# Zio_Qwiic_Relay.net
KiCad netlist of a schematic drawn in EAGLE
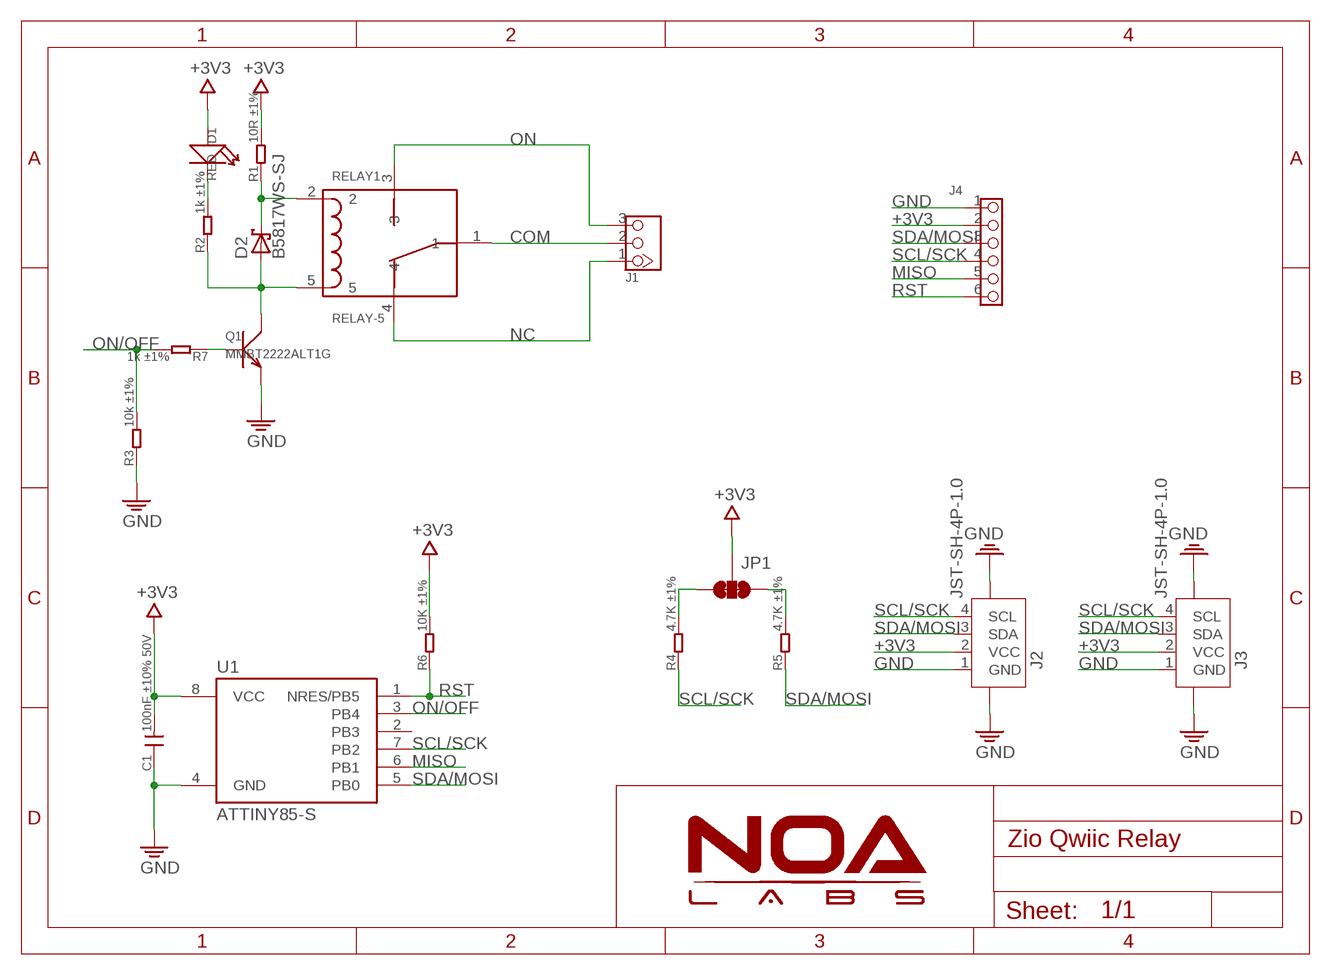
[diagram p0: schematic, sheet 1]

(export (version "E")
  (design (tool "Eeschema 10.0.6"))
  (components
    (comp (ref "C1")
      (value "100nF ±10% 50V")
      (footprint "eagle-import:C0603")
      (libsource (lib "eagle-import") (part "C-0603"))
    )
    (comp (ref "D1")
      (value "RED")
      (footprint "eagle-import:LED-0603")
      (libsource (lib "eagle-import") (part "LED'0603'"))
    )
    (comp (ref "D2")
      (value "B5817WS-SJ")
      (footprint "eagle-import:SOD323")
      (libsource (lib "eagle-import") (part "SCHOTTKY-SOD323"))
    )
    (comp (ref "J1")
      (value "HEADER-3P")
      (footprint "eagle-import:3P-SCREW-5.08")
      (libsource (lib "eagle-import") (part "HEADER-3P"))
    )
    (comp (ref "J2")
      (value "JST-SH-4P-1.0")
      (footprint "eagle-import:JST-SH-4P")
      (libsource (lib "eagle-import") (part "JST-SH-4P-1.0"))
    )
    (comp (ref "J3")
      (value "JST-SH-4P-1.0")
      (footprint "eagle-import:JST-SH-4P")
      (libsource (lib "eagle-import") (part "JST-SH-4P-1.0"))
    )
    (comp (ref "J4")
      (value "HEADER-6P-60/35MIL")
      (footprint "eagle-import:6P-2.54-60_35MIL")
      (libsource (lib "eagle-import") (part "HEADER-6P-60/35MIL"))
    )
    (comp (ref "JP1")
      (value "SMT-JUMPER_3_2-NC_TRACE")
      (footprint "eagle-import:SMT-JUMPER_3_2-NC_TRACE")
      (libsource (lib "eagle-import") (part "SMT-JUMPER_3_2-NC_TRACE"))
    )
    (comp (ref "Q1")
      (value "MMBT2222ALT1G")
      (footprint "eagle-import:SOT23")
      (libsource (lib "eagle-import") (part "TRANSISTOR-NPN-SOT23''"))
    )
    (comp (ref "R1")
      (value "10R ±1%")
      (footprint "eagle-import:R0603")
      (libsource (lib "eagle-import") (part "R-0603"))
    )
    (comp (ref "R2")
      (value "1k ±1%")
      (footprint "eagle-import:R0603")
      (libsource (lib "eagle-import") (part "R-0603"))
    )
    (comp (ref "R3")
      (value "10k ±1%")
      (footprint "eagle-import:R0603")
      (libsource (lib "eagle-import") (part "R-0603"))
    )
    (comp (ref "R4")
      (value "4.7K ±1%")
      (footprint "eagle-import:R0603")
      (libsource (lib "eagle-import") (part "R-0603"))
    )
    (comp (ref "R5")
      (value "4.7K ±1%")
      (footprint "eagle-import:R0603")
      (libsource (lib "eagle-import") (part "R-0603"))
    )
    (comp (ref "R6")
      (value "10K ±1%")
      (footprint "eagle-import:R0603")
      (libsource (lib "eagle-import") (part "R-0603"))
    )
    (comp (ref "R7")
      (value "1k ±1%")
      (footprint "eagle-import:R0603")
      (libsource (lib "eagle-import") (part "R-0603"))
    )
    (comp (ref "RELAY1")
      (value "RELAY-5")
      (footprint "eagle-import:RELAY-5")
      (libsource (lib "eagle-import") (part "RELAY-5"))
    )
    (comp (ref "U1")
      (value "ATTINY85-S")
      (footprint "eagle-import:SOIC8_EIAJ_208MIL")
      (libsource (lib "eagle-import") (part "ATTINY85S-"))
    )
  )
  (nets
    (net (code "1") (name "+3V3") (class "Default")
      (node (ref "C1") (pin "2") (pinfunction "2_2") (pintype "passive"))
      (node (ref "D1") (pin "+") (pinfunction "+_+") (pintype "passive"))
      (node (ref "J2") (pin "2") (pinfunction "VCC_2") (pintype "bidirectional"))
      (node (ref "J3") (pin "2") (pinfunction "VCC_2") (pintype "bidirectional"))
      (node (ref "J4") (pin "2") (pinfunction "2_2") (pintype "bidirectional"))
      (node (ref "JP1") (pin "2") (pinfunction "2_2") (pintype "passive"))
      (node (ref "R1") (pin "2") (pinfunction "2_2") (pintype "passive"))
      (node (ref "R6") (pin "2") (pinfunction "2_2") (pintype "passive"))
      (node (ref "U1") (pin "8") (pinfunction "VCC_8") (pintype "power_in"))
    )
    (net (code "2") (name "/COM") (class "Default")
      (node (ref "J1") (pin "2") (pinfunction "P$2_2") (pintype "bidirectional"))
      (node (ref "RELAY1") (pin "1") (pinfunction "1_1") (pintype "bidirectional"))
    )
    (net (code "3") (name "/MISO") (class "Default")
      (node (ref "J4") (pin "5") (pinfunction "5_5") (pintype "bidirectional"))
      (node (ref "U1") (pin "6") (pinfunction "PB1_6") (pintype "bidirectional"))
    )
    (net (code "4") (name "/NC") (class "Default")
      (node (ref "J1") (pin "1") (pinfunction "P$1_1") (pintype "bidirectional"))
      (node (ref "RELAY1") (pin "4") (pinfunction "4_4") (pintype "bidirectional"))
    )
    (net (code "5") (name "/ON") (class "Default")
      (node (ref "J1") (pin "3") (pinfunction "P$3_3") (pintype "bidirectional"))
      (node (ref "RELAY1") (pin "3") (pinfunction "3_3") (pintype "bidirectional"))
    )
    (net (code "6") (name "/ON{slash}OFF") (class "Default")
      (node (ref "R3") (pin "2") (pinfunction "2_2") (pintype "passive"))
      (node (ref "R7") (pin "2") (pinfunction "2_2") (pintype "passive"))
      (node (ref "U1") (pin "3") (pinfunction "PB4_3") (pintype "bidirectional"))
    )
    (net (code "7") (name "/RST") (class "Default")
      (node (ref "J4") (pin "6") (pinfunction "6_6") (pintype "bidirectional"))
      (node (ref "R6") (pin "1") (pinfunction "1_1") (pintype "passive"))
      (node (ref "U1") (pin "1") (pinfunction "NRES/PB5_1") (pintype "bidirectional"))
    )
    (net (code "8") (name "/SCL{slash}SCK") (class "Default")
      (node (ref "J2") (pin "4") (pinfunction "SCL_4") (pintype "bidirectional"))
      (node (ref "J3") (pin "4") (pinfunction "SCL_4") (pintype "bidirectional"))
      (node (ref "J4") (pin "4") (pinfunction "4_4") (pintype "bidirectional"))
      (node (ref "R4") (pin "1") (pinfunction "1_1") (pintype "passive"))
      (node (ref "U1") (pin "7") (pinfunction "PB2_7") (pintype "bidirectional"))
    )
    (net (code "9") (name "/SDA{slash}MOSI") (class "Default")
      (node (ref "J2") (pin "3") (pinfunction "SDA_3") (pintype "bidirectional"))
      (node (ref "J3") (pin "3") (pinfunction "SDA_3") (pintype "bidirectional"))
      (node (ref "J4") (pin "3") (pinfunction "3_3") (pintype "bidirectional"))
      (node (ref "R5") (pin "1") (pinfunction "1_1") (pintype "passive"))
      (node (ref "U1") (pin "5") (pinfunction "PB0_5") (pintype "bidirectional"))
    )
    (net (code "10") (name "GND") (class "Default")
      (node (ref "C1") (pin "1") (pinfunction "1_1") (pintype "passive"))
      (node (ref "J2") (pin "1") (pinfunction "GND_1") (pintype "bidirectional"))
      (node (ref "J2") (pin "NC1") (pinfunction "5_NC1") (pintype "bidirectional"))
      (node (ref "J2") (pin "NC2") (pinfunction "6_NC2") (pintype "bidirectional"))
      (node (ref "J3") (pin "1") (pinfunction "GND_1") (pintype "bidirectional"))
      (node (ref "J3") (pin "NC1") (pinfunction "5_NC1") (pintype "bidirectional"))
      (node (ref "J3") (pin "NC2") (pinfunction "6_NC2") (pintype "bidirectional"))
      (node (ref "J4") (pin "1") (pinfunction "1_1") (pintype "bidirectional"))
      (node (ref "Q1") (pin "2") (pinfunction "E_2") (pintype "passive"))
      (node (ref "R3") (pin "1") (pinfunction "1_1") (pintype "passive"))
      (node (ref "U1") (pin "4") (pinfunction "GND_4") (pintype "power_in"))
    )
    (net (code "11") (name "Net-(D1-Pad-)") (class "Default")
      (node (ref "D1") (pin "-") (pinfunction "-_-") (pintype "passive"))
      (node (ref "R2") (pin "2") (pinfunction "2_2") (pintype "passive"))
    )
    (net (code "12") (name "Net-(D2-A)") (class "Default")
      (node (ref "D2") (pin "+") (pinfunction "A_+") (pintype "passive"))
      (node (ref "Q1") (pin "3") (pinfunction "C_3") (pintype "passive"))
      (node (ref "R2") (pin "1") (pinfunction "1_1") (pintype "passive"))
      (node (ref "RELAY1") (pin "5") (pinfunction "5_5") (pintype "bidirectional"))
    )
    (net (code "13") (name "Net-(D2-C)") (class "Default")
      (node (ref "D2") (pin "-") (pinfunction "C_-") (pintype "passive"))
      (node (ref "R1") (pin "1") (pinfunction "1_1") (pintype "passive"))
      (node (ref "RELAY1") (pin "2") (pinfunction "2_2") (pintype "bidirectional"))
    )
    (net (code "14") (name "Net-(JP1-Pad1)") (class "Default")
      (node (ref "JP1") (pin "1") (pinfunction "1_1") (pintype "passive"))
      (node (ref "R5") (pin "2") (pinfunction "2_2") (pintype "passive"))
    )
    (net (code "15") (name "Net-(JP1-Pad3)") (class "Default")
      (node (ref "JP1") (pin "3") (pinfunction "3_3") (pintype "passive"))
      (node (ref "R4") (pin "2") (pinfunction "2_2") (pintype "passive"))
    )
    (net (code "16") (name "Net-(Q1-B)") (class "Default")
      (node (ref "Q1") (pin "1") (pinfunction "B_1") (pintype "passive"))
      (node (ref "R7") (pin "1") (pinfunction "1_1") (pintype "passive"))
    )
    (net (code "17") (name "unconnected-(U1-PB3-Pad2)") (class "Default")
      (node (ref "U1") (pin "2") (pinfunction "PB3_2") (pintype "bidirectional"))
    )
  )
)
